# extension_v_1_1.net
KiCad netlist of a schematic drawn in EAGLE
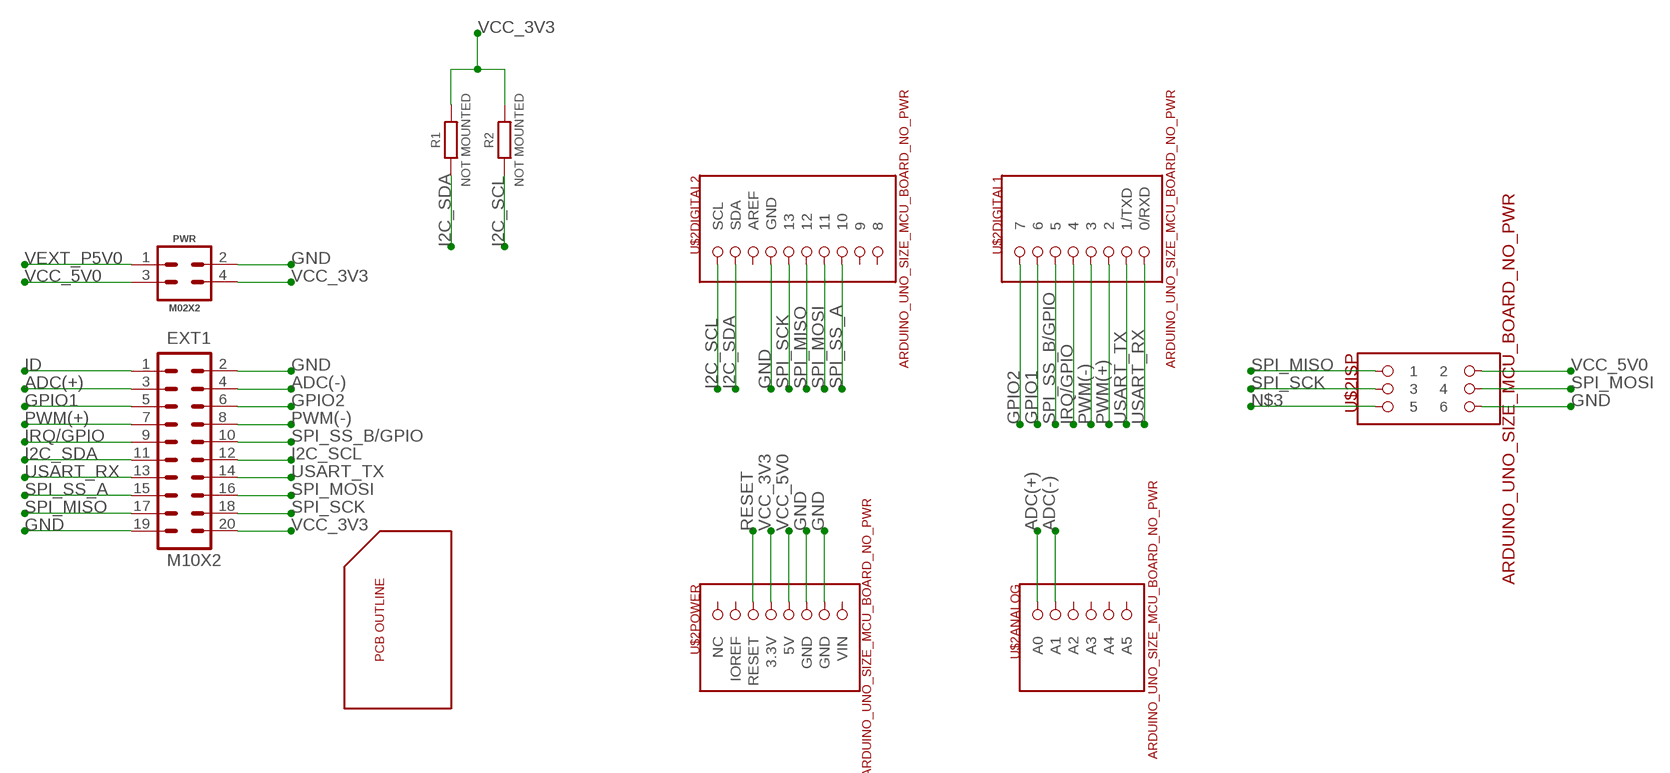
[diagram p0: schematic, sheet 1]

(export (version "E")
  (design (tool "Eeschema 10.0.6"))
  (components
    (comp (ref "EXT1")
      (value "M10X2")
      (footprint "eagle-import:2X10")
      (libsource (lib "eagle-import") (part "M10X2"))
    )
    (comp (ref "PWR")
      (value "M02X2")
      (footprint "eagle-import:H4X2_100_MIL")
      (libsource (lib "eagle-import") (part "M02X2"))
    )
    (comp (ref "R1")
      (value "NOT MOUNTED")
      (footprint "eagle-import:0603")
      (libsource (lib "eagle-import") (part "R0603"))
    )
    (comp (ref "R2")
      (value "NOT MOUNTED")
      (footprint "eagle-import:0603")
      (libsource (lib "eagle-import") (part "R0603"))
    )
    (comp (ref "U$2")
      (value "ARDUINO_UNO_SIZE_MCU_BOARD_NO_PWR")
      (footprint "eagle-import:STANDARD_NO_PWR")
      (libsource (lib "eagle-import") (part "ARDUINO_UNO_SIZE_MCU_BOARD_NO_PWR"))
    )
  )
  (nets
    (net (code "1") (name "/ADC(+)") (class "Default")
      (node (ref "EXT1") (pin "3") (pinfunction "3_3") (pintype "passive"))
      (node (ref "U$2") (pin "9") (pinfunction "A0_9") (pintype "bidirectional"))
    )
    (net (code "2") (name "/ADC(-)") (class "Default")
      (node (ref "EXT1") (pin "4") (pinfunction "4_4") (pintype "passive"))
      (node (ref "U$2") (pin "11") (pinfunction "A1_11") (pintype "bidirectional"))
    )
    (net (code "3") (name "/GND") (class "Default")
      (node (ref "EXT1") (pin "19") (pinfunction "19_19") (pintype "passive"))
      (node (ref "EXT1") (pin "2") (pinfunction "2_2") (pintype "passive"))
      (node (ref "PWR") (pin "2") (pinfunction "2_2") (pintype "bidirectional"))
      (node (ref "U$2") (pin "30") (pinfunction "GND_30") (pintype "bidirectional"))
      (node (ref "U$2") (pin "6") (pinfunction "GND_6") (pintype "bidirectional"))
      (node (ref "U$2") (pin "7") (pinfunction "GND_7") (pintype "bidirectional"))
      (node (ref "U$2") (pin "ISCP6") (pinfunction "6_ISCP6") (pintype "bidirectional"))
    )
    (net (code "4") (name "/GPIO1") (class "Default")
      (node (ref "EXT1") (pin "5") (pinfunction "5_5") (pintype "passive"))
      (node (ref "U$2") (pin "22") (pinfunction "6_22") (pintype "bidirectional"))
    )
    (net (code "5") (name "/GPIO2") (class "Default")
      (node (ref "EXT1") (pin "6") (pinfunction "6_6") (pintype "passive"))
      (node (ref "U$2") (pin "23") (pinfunction "7_23") (pintype "bidirectional"))
    )
    (net (code "6") (name "/I2C_SCL") (class "Default")
      (node (ref "EXT1") (pin "12") (pinfunction "12_12") (pintype "passive"))
      (node (ref "R2") (pin "1") (pinfunction "1_1") (pintype "passive"))
      (node (ref "U$2") (pin "60") (pinfunction "SCL_60") (pintype "bidirectional"))
    )
    (net (code "7") (name "/I2C_SDA") (class "Default")
      (node (ref "EXT1") (pin "11") (pinfunction "11_11") (pintype "passive"))
      (node (ref "R1") (pin "1") (pinfunction "1_1") (pintype "passive"))
      (node (ref "U$2") (pin "50") (pinfunction "SDA_50") (pintype "bidirectional"))
    )
    (net (code "8") (name "/ID") (class "Default")
      (node (ref "EXT1") (pin "1") (pinfunction "1_1") (pintype "passive"))
    )
    (net (code "9") (name "/IRQ{slash}GPIO") (class "Default")
      (node (ref "EXT1") (pin "9") (pinfunction "9_9") (pintype "passive"))
      (node (ref "U$2") (pin "20") (pinfunction "4_20") (pintype "bidirectional"))
    )
    (net (code "10") (name "/N$3") (class "Default")
      (node (ref "U$2") (pin "ISCP5") (pinfunction "5_ISCP5") (pintype "bidirectional"))
    )
    (net (code "11") (name "/PWM(+)") (class "Default")
      (node (ref "EXT1") (pin "7") (pinfunction "7_7") (pintype "passive"))
      (node (ref "U$2") (pin "18") (pinfunction "2_18") (pintype "bidirectional"))
    )
    (net (code "12") (name "/PWM(-)") (class "Default")
      (node (ref "EXT1") (pin "8") (pinfunction "8_8") (pintype "passive"))
      (node (ref "U$2") (pin "19") (pinfunction "3_19") (pintype "bidirectional"))
    )
    (net (code "13") (name "/RESET") (class "Default")
      (node (ref "U$2") (pin "3") (pinfunction "RESET_3") (pintype "bidirectional"))
    )
    (net (code "14") (name "/SPI_MISO") (class "Default")
      (node (ref "EXT1") (pin "17") (pinfunction "17_17") (pintype "passive"))
      (node (ref "U$2") (pin "28") (pinfunction "12_28") (pintype "bidirectional"))
      (node (ref "U$2") (pin "ICSP1") (pinfunction "1_ICSP1") (pintype "bidirectional"))
    )
    (net (code "15") (name "/SPI_MOSI") (class "Default")
      (node (ref "EXT1") (pin "16") (pinfunction "16_16") (pintype "passive"))
      (node (ref "U$2") (pin "27") (pinfunction "11_27") (pintype "bidirectional"))
      (node (ref "U$2") (pin "ISCP4") (pinfunction "4_ISCP4") (pintype "bidirectional"))
    )
    (net (code "16") (name "/SPI_SCK") (class "Default")
      (node (ref "EXT1") (pin "18") (pinfunction "18_18") (pintype "passive"))
      (node (ref "U$2") (pin "29") (pinfunction "13_29") (pintype "bidirectional"))
      (node (ref "U$2") (pin "ISCP3") (pinfunction "3_ISCP3") (pintype "bidirectional"))
    )
    (net (code "17") (name "/SPI_SS_A") (class "Default")
      (node (ref "EXT1") (pin "15") (pinfunction "15_15") (pintype "passive"))
      (node (ref "U$2") (pin "26") (pinfunction "10_26") (pintype "bidirectional"))
    )
    (net (code "18") (name "/SPI_SS_B{slash}GPIO") (class "Default")
      (node (ref "EXT1") (pin "10") (pinfunction "10_10") (pintype "passive"))
      (node (ref "U$2") (pin "21") (pinfunction "5_21") (pintype "bidirectional"))
    )
    (net (code "19") (name "/USART_RX") (class "Default")
      (node (ref "EXT1") (pin "13") (pinfunction "13_13") (pintype "passive"))
      (node (ref "U$2") (pin "16") (pinfunction "0/RXD_16") (pintype "bidirectional"))
    )
    (net (code "20") (name "/USART_TX") (class "Default")
      (node (ref "EXT1") (pin "14") (pinfunction "14_14") (pintype "passive"))
      (node (ref "U$2") (pin "17") (pinfunction "1/TXD_17") (pintype "bidirectional"))
    )
    (net (code "21") (name "/VCC_3V3") (class "Default")
      (node (ref "EXT1") (pin "20") (pinfunction "20_20") (pintype "passive"))
      (node (ref "PWR") (pin "4") (pinfunction "4_4") (pintype "bidirectional"))
      (node (ref "R1") (pin "2") (pinfunction "2_2") (pintype "passive"))
      (node (ref "R2") (pin "2") (pinfunction "2_2") (pintype "passive"))
      (node (ref "U$2") (pin "4") (pinfunction "3.3V_4") (pintype "bidirectional"))
    )
    (net (code "22") (name "/VCC_5V0") (class "Default")
      (node (ref "PWR") (pin "3") (pinfunction "3_3") (pintype "bidirectional"))
      (node (ref "U$2") (pin "5") (pinfunction "5V_5") (pintype "bidirectional"))
      (node (ref "U$2") (pin "ICSP2") (pinfunction "2_ICSP2") (pintype "bidirectional"))
    )
    (net (code "23") (name "/VEXT_P5V0") (class "Default")
      (node (ref "PWR") (pin "1") (pinfunction "1_1") (pintype "bidirectional"))
    )
    (net (code "24") (name "unconnected-(U$2A-A2-Pad12)") (class "Default")
      (node (ref "U$2") (pin "12") (pinfunction "A2_12") (pintype "bidirectional"))
    )
    (net (code "25") (name "unconnected-(U$2A-A3-Pad13)") (class "Default")
      (node (ref "U$2") (pin "13") (pinfunction "A3_13") (pintype "bidirectional"))
    )
    (net (code "26") (name "unconnected-(U$2A-A4-Pad14)") (class "Default")
      (node (ref "U$2") (pin "14") (pinfunction "A4_14") (pintype "bidirectional"))
    )
    (net (code "27") (name "unconnected-(U$2A-A5-Pad15)") (class "Default")
      (node (ref "U$2") (pin "15") (pinfunction "A5_15") (pintype "bidirectional"))
    )
    (net (code "28") (name "unconnected-(U$2C-8-Pad24)") (class "Default")
      (node (ref "U$2") (pin "24") (pinfunction "8_24") (pintype "bidirectional"))
    )
    (net (code "29") (name "unconnected-(U$2C-9-Pad25)") (class "Default")
      (node (ref "U$2") (pin "25") (pinfunction "9_25") (pintype "bidirectional"))
    )
    (net (code "30") (name "unconnected-(U$2C-AREF-Pad40)") (class "Default")
      (node (ref "U$2") (pin "40") (pinfunction "AREF_40") (pintype "bidirectional"))
    )
    (net (code "31") (name "unconnected-(U$2F-IOREF-Pad2)") (class "Default")
      (node (ref "U$2") (pin "2") (pinfunction "IOREF_2") (pintype "bidirectional"))
    )
    (net (code "32") (name "unconnected-(U$2F-NC-Pad1)") (class "Default")
      (node (ref "U$2") (pin "1") (pinfunction "NC_1") (pintype "bidirectional"))
    )
    (net (code "33") (name "unconnected-(U$2F-VIN-Pad8)") (class "Default")
      (node (ref "U$2") (pin "8") (pinfunction "VIN_8") (pintype "bidirectional"))
    )
  )
)
